# LilyPad_SimplePower_45_degree_for_paneli.net
KiCad netlist of a schematic drawn in EAGLE
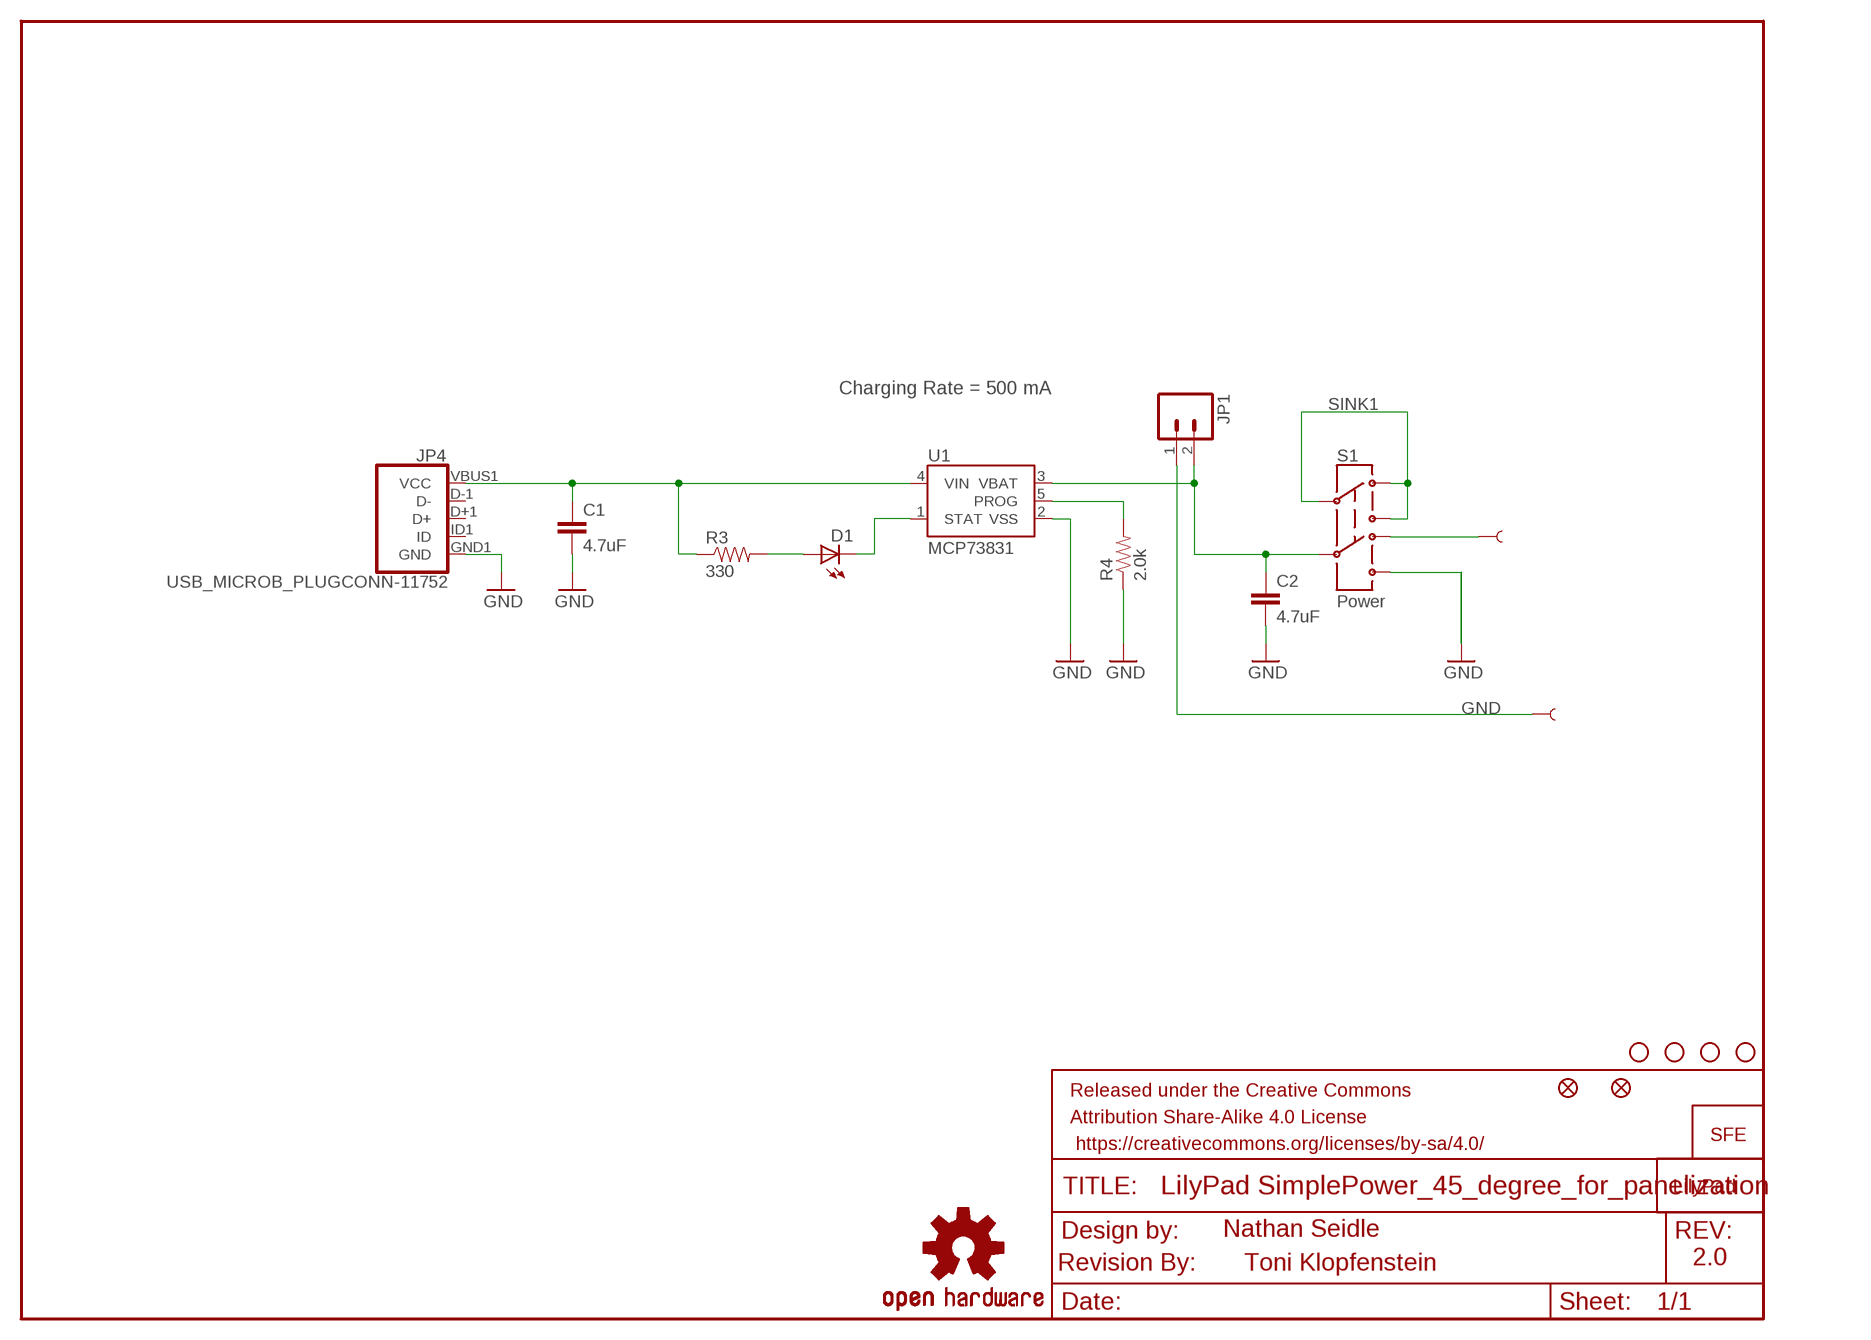
[diagram p0: schematic, sheet 1]

(export (version "E")
  (design (tool "Eeschema 10.0.6"))
  (components
    (comp (ref "C1")
      (value "4.7uF")
      (footprint "eagle-import:0603-CAP")
      (libsource (lib "eagle-import") (part "4.7UF-6.3V-10%(0603)0603"))
    )
    (comp (ref "C2")
      (value "4.7uF")
      (footprint "eagle-import:0603-CAP")
      (libsource (lib "eagle-import") (part "4.7UF-6.3V-10%(0603)0603"))
    )
    (comp (ref "D1")
      (value "LED-YELLOW0603")
      (footprint "eagle-import:LED-0603")
      (libsource (lib "eagle-import") (part "LED-YELLOW0603"))
    )
    (comp (ref "FID1")
      (value "FIDUCIAL1X2")
      (footprint "eagle-import:FIDUCIAL-1X2")
      (libsource (lib "eagle-import") (part "FIDUCIAL1X2"))
    )
    (comp (ref "FID2")
      (value "FIDUCIAL1X2")
      (footprint "eagle-import:FIDUCIAL-1X2")
      (libsource (lib "eagle-import") (part "FIDUCIAL1X2"))
    )
    (comp (ref "FRAME1")
      (value "FRAME-LETTER")
      (footprint "eagle-import:CREATIVE_COMMONS")
      (libsource (lib "eagle-import") (part "FRAME-LETTER"))
    )
    (comp (ref "JP1")
      (value "M02-JST-2MM-SMT")
      (footprint "eagle-import:JST-2-SMD")
      (libsource (lib "eagle-import") (part "M02-JST-2MM-SMT"))
    )
    (comp (ref "JP3")
      (value "LOGO-SFESK")
      (footprint "eagle-import:SFE-LOGO-FLAME")
      (libsource (lib "eagle-import") (part "LOGO-SFESK"))
    )
    (comp (ref "JP4")
      (value "USB_MICROB_PLUGCONN-11752")
      (footprint "eagle-import:USB-B-MICRO-SMD_V03")
      (libsource (lib "eagle-import") (part "USB_MICROB_PLUGCONN-11752"))
    )
    (comp (ref "R3")
      (value "330")
      (footprint "eagle-import:0603-RES")
      (libsource (lib "eagle-import") (part "330OHM1/10W1%(0603)"))
    )
    (comp (ref "R4")
      (value "2.0k")
      (footprint "eagle-import:0603-RES")
      (libsource (lib "eagle-import") (part "2.0KOHM1/10W5%(0603)"))
    )
    (comp (ref "S1")
      (value "Power")
      (footprint "eagle-import:AYZ0202")
      (libsource (lib "eagle-import") (part "SWITCH-DPDTSMD"))
    )
    (comp (ref "STANDOFF1")
      (value "SEW-HOLE-NO-PAD")
      (footprint "eagle-import:SEW-HOLE-NO-PAD")
      (libsource (lib "eagle-import") (part "SEW-HOLE-NO-PAD"))
    )
    (comp (ref "STANDOFF2")
      (value "SEW-HOLE-NO-PAD")
      (footprint "eagle-import:SEW-HOLE-NO-PAD")
      (libsource (lib "eagle-import") (part "SEW-HOLE-NO-PAD"))
    )
    (comp (ref "STANDOFF3")
      (value "SEW-HOLE-NO-PAD")
      (footprint "eagle-import:SEW-HOLE-NO-PAD")
      (libsource (lib "eagle-import") (part "SEW-HOLE-NO-PAD"))
    )
    (comp (ref "STANDOFF4")
      (value "SEW-HOLE-NO-PAD")
      (footprint "eagle-import:SEW-HOLE-NO-PAD")
      (libsource (lib "eagle-import") (part "SEW-HOLE-NO-PAD"))
    )
    (comp (ref "U$1")
      (value "LOGO-LPLP")
      (footprint "eagle-import:LOGO-LILYPAD")
      (libsource (lib "eagle-import") (part "LOGO-LPLP"))
    )
    (comp (ref "U$3")
      (value "SEWTAP9")
      (footprint "eagle-import:PETAL-LONG-1-2SIDE")
      (libsource (lib "eagle-import") (part "SEWTAP9"))
    )
    (comp (ref "U$4")
      (value "SEWTAP9")
      (footprint "eagle-import:PETAL-LONG-1-2SIDE")
      (libsource (lib "eagle-import") (part "SEWTAP9"))
    )
    (comp (ref "U$5")
      (value "OSHW-LOGOS")
      (footprint "eagle-import:OSHW-LOGO-S")
      (libsource (lib "eagle-import") (part "OSHW-LOGOS"))
    )
    (comp (ref "U$6")
      (value "REVISION")
      (footprint "eagle-import:REVISION")
      (libsource (lib "eagle-import") (part "REVISION"))
    )
    (comp (ref "U1")
      (value "MCP73831")
      (footprint "eagle-import:SOT23-5")
      (libsource (lib "eagle-import") (part "MCP73831"))
    )
  )
  (nets
    (net (code "1") (name "/SINK1") (class "Default")
      (node (ref "S1") (pin "1") (pinfunction "1_1") (pintype "bidirectional"))
      (node (ref "S1") (pin "2") (pinfunction "2_2") (pintype "bidirectional"))
      (node (ref "S1") (pin "3") (pinfunction "3_3") (pintype "bidirectional"))
    )
    (net (code "2") (name "GND") (class "Default")
      (node (ref "C1") (pin "2") (pinfunction "2_2") (pintype "passive"))
      (node (ref "C2") (pin "2") (pinfunction "2_2") (pintype "passive"))
      (node (ref "JP1") (pin "1") (pinfunction "1_1") (pintype "passive"))
      (node (ref "JP4") (pin "GND1") (pinfunction "GND_GND1") (pintype "bidirectional"))
      (node (ref "R4") (pin "1") (pinfunction "1_1") (pintype "passive"))
      (node (ref "S1") (pin "6") (pinfunction "6_6") (pintype "bidirectional"))
      (node (ref "U$3") (pin "1") (pinfunction "1_1") (pintype "bidirectional"))
      (node (ref "U1") (pin "2") (pinfunction "VSS_2") (pintype "power_in"))
    )
    (net (code "3") (name "Net-(D1-PadA)") (class "Default")
      (node (ref "D1") (pin "A") (pinfunction "A_A") (pintype "passive"))
      (node (ref "R3") (pin "2") (pinfunction "2_2") (pintype "passive"))
    )
    (net (code "4") (name "Net-(JP4-VCC)") (class "Default")
      (node (ref "C1") (pin "1") (pinfunction "1_1") (pintype "passive"))
      (node (ref "JP4") (pin "VBUS1") (pinfunction "VCC_VBUS1") (pintype "bidirectional"))
      (node (ref "R3") (pin "1") (pinfunction "1_1") (pintype "passive"))
      (node (ref "U1") (pin "4") (pinfunction "VIN_4") (pintype "power_in"))
    )
    (net (code "5") (name "Net-(S1-Pad4)") (class "Default")
      (node (ref "S1") (pin "4") (pinfunction "4_4") (pintype "bidirectional"))
      (node (ref "U$4") (pin "1") (pinfunction "1_1") (pintype "bidirectional"))
    )
    (net (code "6") (name "Net-(U1-PROG)") (class "Default")
      (node (ref "R4") (pin "2") (pinfunction "2_2") (pintype "passive"))
      (node (ref "U1") (pin "5") (pinfunction "PROG_5") (pintype "input"))
    )
    (net (code "7") (name "Net-(U1-STAT)") (class "Default")
      (node (ref "D1") (pin "C") (pinfunction "C_C") (pintype "passive"))
      (node (ref "U1") (pin "1") (pinfunction "STAT_1") (pintype "output"))
    )
    (net (code "8") (name "Net-(U1-VBAT)") (class "Default")
      (node (ref "C2") (pin "1") (pinfunction "1_1") (pintype "passive"))
      (node (ref "JP1") (pin "2") (pinfunction "2_2") (pintype "passive"))
      (node (ref "S1") (pin "5") (pinfunction "5_5") (pintype "bidirectional"))
      (node (ref "U1") (pin "3") (pinfunction "VBAT_3") (pintype "power_in"))
    )
    (net (code "9") (name "unconnected-(JP4-D+-PadD+1)") (class "Default")
      (node (ref "JP4") (pin "D+1") (pinfunction "D+_D+1") (pintype "bidirectional"))
    )
    (net (code "10") (name "unconnected-(JP4-D--PadD-1)") (class "Default")
      (node (ref "JP4") (pin "D-1") (pinfunction "D-_D-1") (pintype "bidirectional"))
    )
    (net (code "11") (name "unconnected-(JP4-ID-PadID1)") (class "Default")
      (node (ref "JP4") (pin "ID1") (pinfunction "ID_ID1") (pintype "bidirectional"))
    )
  )
)
